# 464421_22-01_RF_IN.net
KiCad netlist of a schematic drawn in Altium Designer
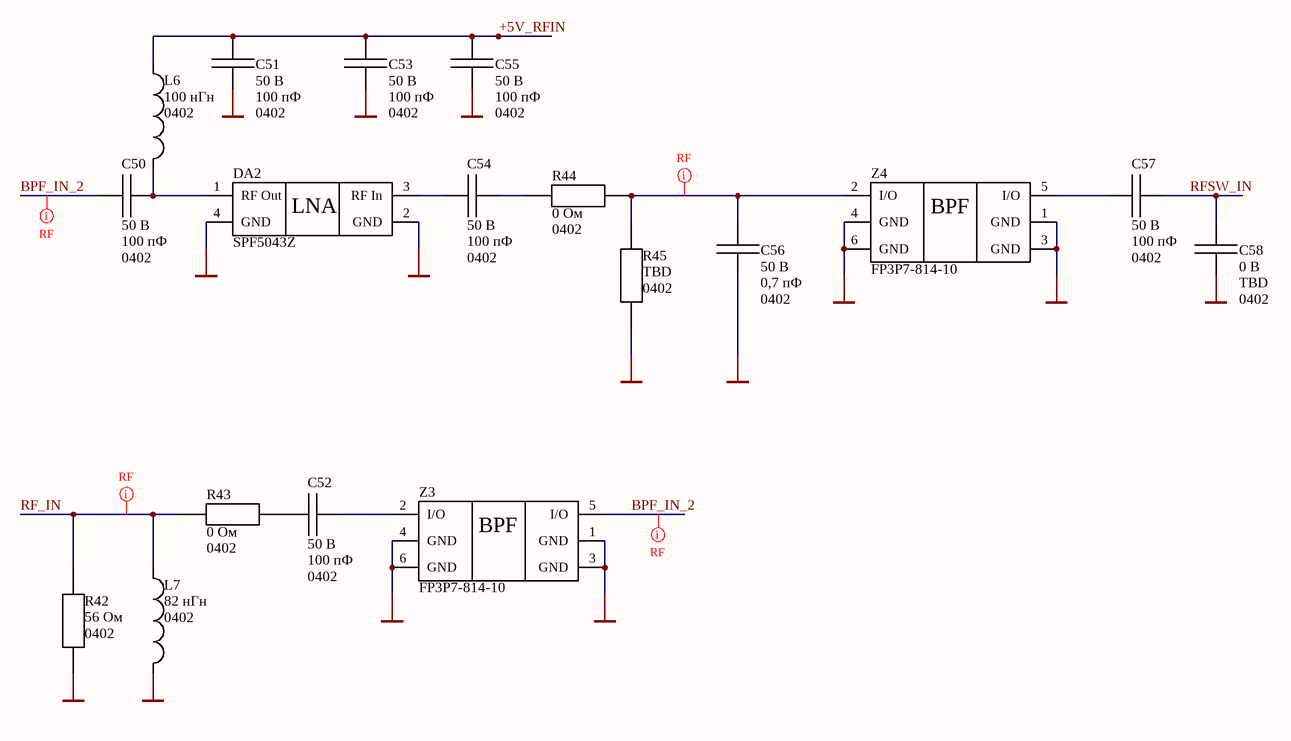
[diagram p0: МПСУ.464421.22-01 RF_IN.SchDoc]

(export (version "E")
  (design (tool "Eeschema 10.0.6"))
  (components
    (comp (ref "C50")
      (value "100 пФ")
      (footprint "Passive_V2_0:CAPC100X50X55L20N")
      (description "Capacitor 0402")
      (fields
        (field (name "PARTNUMBER") "GRM1555C1H101JZ01D")
        (field (name "MANUFACTURER") "Murata")
        (field (name "PEAK_CONDITION") "50 В")
        (field (name "PACKAGE") "0402")
        (field (name "DESIGNER") "Свидерский")
      )
      (libsource (lib "Passive_V2_0") (part "C 0402"))
    )
    (comp (ref "C51")
      (value "100 пФ")
      (footprint "Passive_V2_0:CAPC100X50X55L20N")
      (description "Capacitor 0402")
      (fields
        (field (name "PARTNUMBER") "GRM1555C1H101JZ01D")
        (field (name "MANUFACTURER") "Murata")
        (field (name "PEAK_CONDITION") "50 В")
        (field (name "PACKAGE") "0402")
        (field (name "DESIGNER") "Свидерский")
      )
      (libsource (lib "Passive_V2_0") (part "C 0402"))
    )
    (comp (ref "C52")
      (value "100 пФ")
      (footprint "Passive_V2_0:CAPC100X50X55L20N")
      (description "Capacitor 0402")
      (fields
        (field (name "PARTNUMBER") "GRM1555C1H101JZ01D")
        (field (name "MANUFACTURER") "Murata")
        (field (name "PEAK_CONDITION") "50 В")
        (field (name "PACKAGE") "0402")
        (field (name "DESIGNER") "Свидерский")
      )
      (libsource (lib "Passive_V2_0") (part "C 0402"))
    )
    (comp (ref "C53")
      (value "100 пФ")
      (footprint "Passive_V2_0:CAPC100X50X55L20N")
      (description "Capacitor 0402")
      (fields
        (field (name "PARTNUMBER") "GRM1555C1H101JZ01D")
        (field (name "MANUFACTURER") "Murata")
        (field (name "PEAK_CONDITION") "50 В")
        (field (name "PACKAGE") "0402")
        (field (name "DESIGNER") "Свидерский")
      )
      (libsource (lib "Passive_V2_0") (part "C 0402"))
    )
    (comp (ref "C54")
      (value "100 пФ")
      (footprint "Passive_V2_0:CAPC100X50X55L20N")
      (description "Capacitor 0402")
      (fields
        (field (name "PARTNUMBER") "GRM1555C1H101JZ01D")
        (field (name "MANUFACTURER") "Murata")
        (field (name "PEAK_CONDITION") "50 В")
        (field (name "PACKAGE") "0402")
        (field (name "DESIGNER") "Свидерский")
      )
      (libsource (lib "Passive_V2_0") (part "C 0402"))
    )
    (comp (ref "C55")
      (value "100 пФ")
      (footprint "Passive_V2_0:CAPC100X50X55L20N")
      (description "Capacitor 0402")
      (fields
        (field (name "PARTNUMBER") "GRM1555C1H101JZ01D")
        (field (name "MANUFACTURER") "Murata")
        (field (name "PEAK_CONDITION") "50 В")
        (field (name "PACKAGE") "0402")
        (field (name "DESIGNER") "Свидерский")
      )
      (libsource (lib "Passive_V2_0") (part "C 0402"))
    )
    (comp (ref "C56")
      (value "0,7 пФ")
      (footprint "Passive_V2_0:CAPC100X50X55L20N")
      (description "Capacitor 0402")
      (fields
        (field (name "PARTNUMBER") "GRM1555C1HR70WA01D")
        (field (name "MANUFACTURER") "Murata")
        (field (name "PEAK_CONDITION") "50 В")
        (field (name "PACKAGE") "0402")
        (field (name "DESIGNER") "Свидерский")
      )
      (libsource (lib "Passive_V2_0") (part "C 0402"))
    )
    (comp (ref "C57")
      (value "100 пФ")
      (footprint "Passive_V2_0:CAPC100X50X55L20N")
      (description "Capacitor 0402")
      (fields
        (field (name "PARTNUMBER") "GRM1555C1H101JZ01D")
        (field (name "MANUFACTURER") "Murata")
        (field (name "PEAK_CONDITION") "50 В")
        (field (name "PACKAGE") "0402")
        (field (name "DESIGNER") "Свидерский")
      )
      (libsource (lib "Passive_V2_0") (part "C 0402"))
    )
    (comp (ref "C58")
      (value "TBD")
      (footprint "Passive_V2_0:CAPC100X50X55L20N")
      (description "Capacitor 0402")
      (fields
        (field (name "TOLERANCE") "0 %")
        (field (name "PEAK_CONDITION") "0 В")
        (field (name "PACKAGE") "0402")
        (field (name "Comment") "TBD 0402")
        (field (name "DESIGNER") "Свидерский")
      )
      (libsource (lib "Passive_V2_0") (part "C 0402"))
    )
    (comp (ref "DA2")
      (value "SPF5043Z")
      (footprint "IC_V2_0:SOT130P210X100-4N")
      (description "50 MHz to 4000 MHz Low-Noise Amplifier")
      (fields
        (field (name "MANUFACTURER") "Qorvo")
        (field (name "PARTNUMBER") "SPF5043Z")
        (field (name "DESIGNER") "Лазба")
      )
      (libsource (lib "IC_V2_0") (part "SPF5043Z"))
    )
    (comp (ref "L6")
      (value "100 нГн")
      (footprint "Passive_V2_0:INDC100X50X60L10N")
      (description "Inductor 0402")
      (fields
        (field (name "PARTNUMBER") "LQG15HNR10J02D")
        (field (name "TOLERANCE") "5 %")
        (field (name "PACKAGE") "0402")
        (field (name "DESIGNER") "Свидерский")
      )
      (libsource (lib "Passive_V2_0") (part "L 0402"))
    )
    (comp (ref "L7")
      (value "82 нГн")
      (footprint "Passive_V2_0:INDC100X50X60L10N")
      (description "Inductor 0402")
      (fields
        (field (name "PARTNUMBER") "LQG15HN82NJ02D")
        (field (name "TOLERANCE") "5 %")
        (field (name "PACKAGE") "0402")
        (field (name "DESIGNER") "Свидерский")
      )
      (libsource (lib "Passive_V2_0") (part "L 0402"))
    )
    (comp (ref "R42")
      (value "56 Ом")
      (footprint "Passive_V2_0:RESC100X50X40L25N")
      (description "Resistor 0402")
      (fields
        (field (name "PARTNUMBER") "CR-02FL6-56R")
        (field (name "TOLERANCE") "1 %")
        (field (name "PACKAGE") "0402")
        (field (name "DESIGNER") "Свидерский")
      )
      (libsource (lib "") (part "R 0402_1"))
    )
    (comp (ref "R43")
      (value "0 Ом")
      (footprint "Passive_V2_0:RESC100X50X40L25N")
      (description "Resistor 0402")
      (fields
        (field (name "PARTNUMBER") "RI0402L000JT")
        (field (name "TOLERANCE") "5 %")
        (field (name "PACKAGE") "0402")
        (field (name "DESIGNER") "Свидерский")
      )
      (libsource (lib "Passive_V2_0") (part "R 0402"))
    )
    (comp (ref "R44")
      (value "0 Ом")
      (footprint "Passive_V2_0:RESC100X50X40L25N")
      (description "Resistor 0402")
      (fields
        (field (name "PARTNUMBER") "RI0402L000JT")
        (field (name "TOLERANCE") "5 %")
        (field (name "PACKAGE") "0402")
        (field (name "DESIGNER") "Свидерский")
      )
      (libsource (lib "Passive_V2_0") (part "R 0402"))
    )
    (comp (ref "R45")
      (value "TBD")
      (footprint "Passive_V2_0:RESC100X50X40L25N")
      (description "Resistor 0402")
      (fields
        (field (name "TOLERANCE") "0 %")
        (field (name "PACKAGE") "0402")
        (field (name "Comment") "TBD 0402")
        (field (name "DESIGNER") "Свидерский")
      )
      (libsource (lib "") (part "R 0402_1"))
    )
    (comp (ref "Z3")
      (value "FP3P7-814-10")
      (footprint "Passive_V2_0:LCCS110P300X300X146-6N")
      (description "BandPass Filter")
      (fields
        (field (name "MANUFACTURER") "БУТИС")
        (field (name "PARTNUMBER") "FP3P7-814-10")
        (field (name "DESIGNER") "Лазба")
      )
      (libsource (lib "Passive_V2_0") (part "FP3P7-***-**"))
    )
    (comp (ref "Z4")
      (value "FP3P7-814-10")
      (footprint "Passive_V2_0:LCCS110P300X300X146-6N")
      (description "BandPass Filter")
      (fields
        (field (name "MANUFACTURER") "БУТИС")
        (field (name "PARTNUMBER") "FP3P7-814-10")
        (field (name "DESIGNER") "Лазба")
      )
      (libsource (lib "Passive_V2_0") (part "FP3P7-***-**"))
    )
  )
  (nets
    (net (code "1") (name "/+5V_RFIN") (class "Default")
      (node (ref "C51") (pin "1") (pinfunction "1_1") (pintype "passive"))
      (node (ref "C53") (pin "1") (pinfunction "1_1") (pintype "passive"))
      (node (ref "C55") (pin "1") (pinfunction "1_1") (pintype "passive"))
      (node (ref "L6") (pin "1") (pinfunction "1_1") (pintype "passive"))
    )
    (net (code "2") (name "/BPF_IN_2") (class "Default")
      (node (ref "C50") (pin "1") (pinfunction "1_1") (pintype "passive"))
      (node (ref "Z3") (pin "5") (pinfunction "I/O_5") (pintype "passive"))
    )
    (net (code "3") (name "/RFSW_IN") (class "Default")
      (node (ref "C57") (pin "2") (pinfunction "2_2") (pintype "passive"))
      (node (ref "C58") (pin "1") (pinfunction "1_1") (pintype "passive"))
    )
    (net (code "4") (name "/RF_IN") (class "Default")
      (node (ref "L7") (pin "1") (pinfunction "1_1") (pintype "passive"))
      (node (ref "R42") (pin "1") (pinfunction "1_1") (pintype "passive"))
      (node (ref "R43") (pin "2") (pinfunction "2_2") (pintype "passive"))
    )
    (net (code "5") (name "GND") (class "Default")
      (node (ref "C51") (pin "2") (pinfunction "2_2") (pintype "passive"))
      (node (ref "C53") (pin "2") (pinfunction "2_2") (pintype "passive"))
      (node (ref "C55") (pin "2") (pinfunction "2_2") (pintype "passive"))
      (node (ref "C56") (pin "1") (pinfunction "1_1") (pintype "passive"))
      (node (ref "C58") (pin "2") (pinfunction "2_2") (pintype "passive"))
      (node (ref "DA2") (pin "2") (pinfunction "GND_2") (pintype "passive"))
      (node (ref "DA2") (pin "4") (pinfunction "GND_4") (pintype "passive"))
      (node (ref "L7") (pin "2") (pinfunction "2_2") (pintype "passive"))
      (node (ref "R42") (pin "2") (pinfunction "2_2") (pintype "passive"))
      (node (ref "R45") (pin "2") (pinfunction "2_2") (pintype "passive"))
      (node (ref "Z3") (pin "1") (pinfunction "GND_1") (pintype "passive"))
      (node (ref "Z3") (pin "3") (pinfunction "GND_3") (pintype "passive"))
      (node (ref "Z3") (pin "4") (pinfunction "GND_4") (pintype "passive"))
      (node (ref "Z3") (pin "6") (pinfunction "GND_6") (pintype "passive"))
      (node (ref "Z4") (pin "1") (pinfunction "GND_1") (pintype "passive"))
      (node (ref "Z4") (pin "3") (pinfunction "GND_3") (pintype "passive"))
      (node (ref "Z4") (pin "4") (pinfunction "GND_4") (pintype "passive"))
      (node (ref "Z4") (pin "6") (pinfunction "GND_6") (pintype "passive"))
    )
    (net (code "6") (name "Net-(C52-Pad1)") (class "Default")
      (node (ref "C52") (pin "1") (pinfunction "1_1") (pintype "passive"))
      (node (ref "R43") (pin "1") (pinfunction "1_1") (pintype "passive"))
    )
    (net (code "7") (name "Net-(C52-Pad2)") (class "Default")
      (node (ref "C52") (pin "2") (pinfunction "2_2") (pintype "passive"))
      (node (ref "Z3") (pin "2") (pinfunction "I/O_2") (pintype "passive"))
    )
    (net (code "8") (name "Net-(C54-Pad2)") (class "Default")
      (node (ref "C54") (pin "2") (pinfunction "2_2") (pintype "passive"))
      (node (ref "R44") (pin "2") (pinfunction "2_2") (pintype "passive"))
    )
    (net (code "9") (name "Net-(C56-Pad2)") (class "Default")
      (node (ref "C56") (pin "2") (pinfunction "2_2") (pintype "passive"))
      (node (ref "R44") (pin "1") (pinfunction "1_1") (pintype "passive"))
      (node (ref "R45") (pin "1") (pinfunction "1_1") (pintype "passive"))
      (node (ref "Z4") (pin "2") (pinfunction "I/O_2") (pintype "passive"))
    )
    (net (code "10") (name "Net-(C57-Pad1)") (class "Default")
      (node (ref "C57") (pin "1") (pinfunction "1_1") (pintype "passive"))
      (node (ref "Z4") (pin "5") (pinfunction "I/O_5") (pintype "passive"))
    )
    (net (code "11") (name "Net-(DA2-RF_In)") (class "Default")
      (node (ref "C54") (pin "1") (pinfunction "1_1") (pintype "passive"))
      (node (ref "DA2") (pin "3") (pinfunction "RF_In_3") (pintype "passive"))
    )
    (net (code "12") (name "Net-(DA2-RF_Out)") (class "Default")
      (node (ref "C50") (pin "2") (pinfunction "2_2") (pintype "passive"))
      (node (ref "DA2") (pin "1") (pinfunction "RF_Out_1") (pintype "passive"))
      (node (ref "L6") (pin "2") (pinfunction "2_2") (pintype "passive"))
    )
  )
)
